# SUP_3_3_FMC.net
KiCad netlist of a schematic drawn in Altium Designer
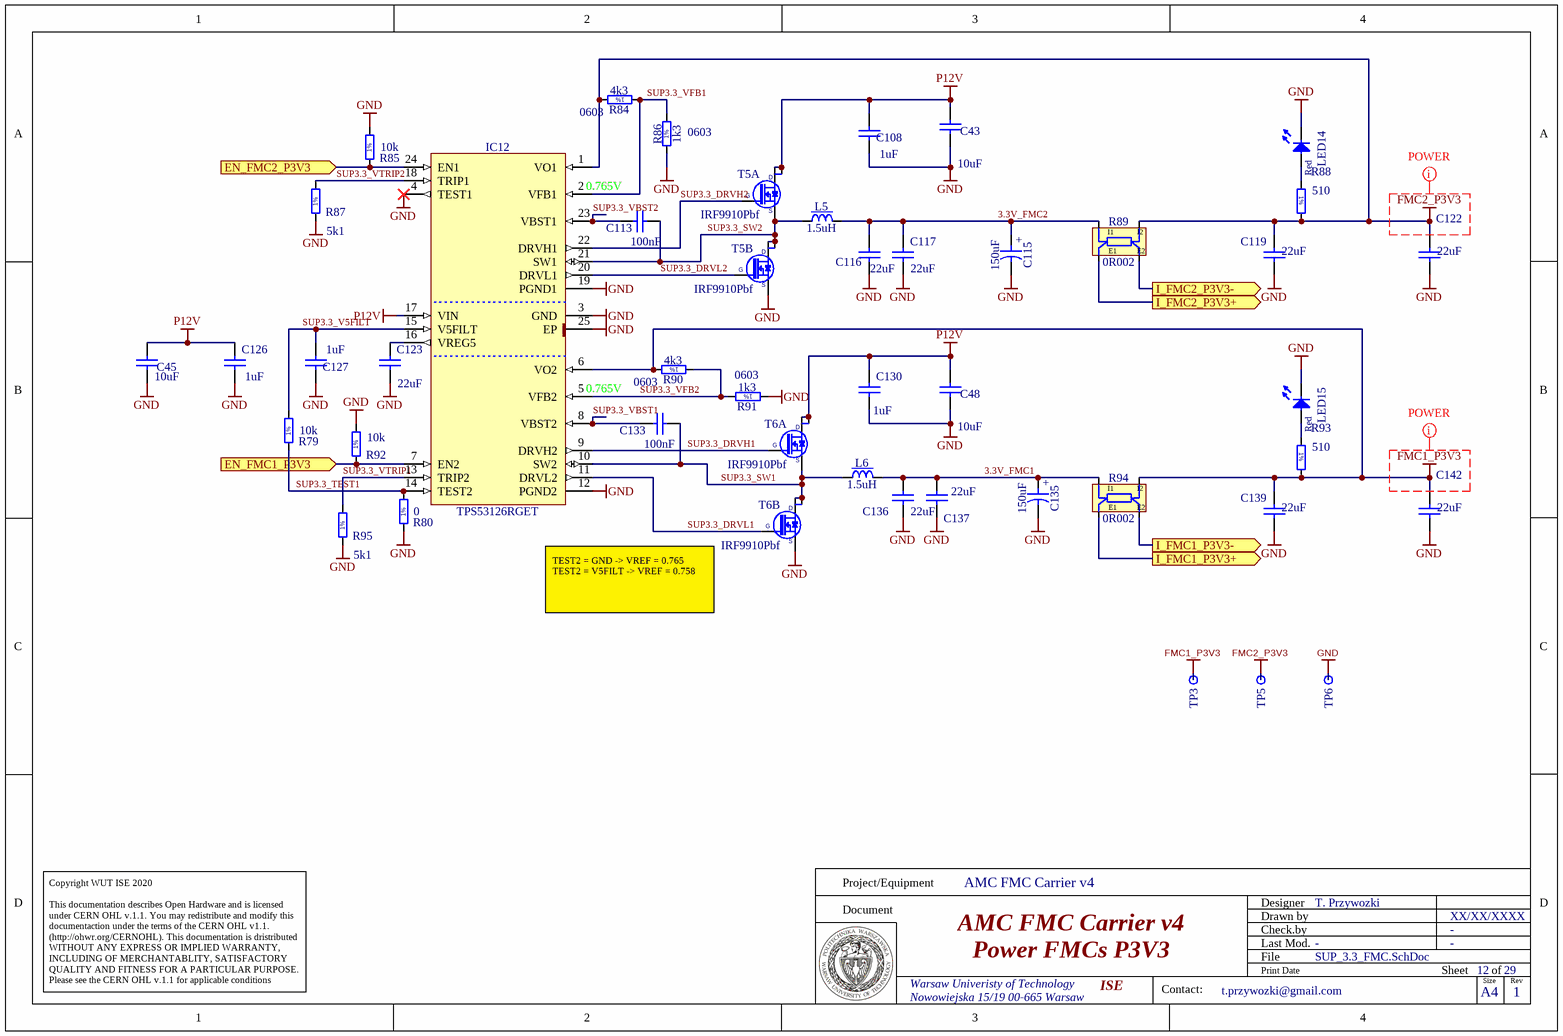
[diagram p0: SUP_3.3_FMC.SchDoc]

(export (version "E")
  (design (tool "Eeschema 10.0.6"))
  (components
    (comp (ref "C43")
      (value "10uF")
      (footprint "CAPC2012X135N")
      (description "Non-polarised capacitor")
      (fields
        (field (name "PART NUMBER") "CC0805_10UF_16V_10%_X5R")
        (field (name "VOLTAGE") "16V")
        (field (name "AUTHOR") "CERN DEM JLC")
      )
      (libsource (lib "Capacitors") (part "Capacitor - non polarized"))
    )
    (comp (ref "C45")
      (value "10uF")
      (footprint "CAPC2012X135N")
      (description "Non-polarised capacitor")
      (fields
        (field (name "PART NUMBER") "CC0805_10UF_16V_10%_X5R")
        (field (name "VOLTAGE") "16V")
        (field (name "AUTHOR") "CERN DEM JLC")
      )
      (libsource (lib "Capacitors") (part "Capacitor - non polarized"))
    )
    (comp (ref "C48")
      (value "10uF")
      (footprint "CAPC2012X135N")
      (description "Non-polarised capacitor")
      (fields
        (field (name "PART NUMBER") "CC0805_10UF_16V_10%_X5R")
        (field (name "VOLTAGE") "16V")
        (field (name "AUTHOR") "CERN DEM JLC")
      )
      (libsource (lib "Capacitors") (part "Capacitor - non polarized"))
    )
    (comp (ref "C108")
      (value "1uF")
      (footprint "CAPC1608X87N")
      (description "Non-polarised capacitor")
      (fields
        (field (name "PART NUMBER") "CC0603_1UF_16V_10%_X7R")
        (field (name "VOLTAGE") "16V")
        (field (name "AUTHOR") "CERN DEM JLC")
      )
      (libsource (lib "Capacitors") (part "Capacitor - non polarized"))
    )
    (comp (ref "C113")
      (value "100nF")
      (footprint "CAPC1005X55N")
      (description "Non-polarised capacitor")
      (fields
        (field (name "PART NUMBER") "CC0402_100NF_16V_10%_X7R")
        (field (name "VOLTAGE") "16V")
        (field (name "AUTHOR") "CERN DEM JLC")
      )
      (libsource (lib "Capacitors") (part "Capacitor - non polarized"))
    )
    (comp (ref "C115")
      (value "150uF")
      (footprint "CAPMP7343X200N")
      (description "Polarised capacitor")
      (fields
        (field (name "PART NUMBER") "CAEM7343-20_150UF_4V_20%_LESR0016")
        (field (name "VOLTAGE") "4V")
        (field (name "AUTHOR") "CERN DEM JLC")
      )
      (libsource (lib "Capacitors") (part "Capacitor - polarized"))
    )
    (comp (ref "C116")
      (value "22uF")
      (footprint "CAPC3216X180N")
      (description "Non-polarised capacitor")
      (fields
        (field (name "PART NUMBER") "CC1206_22UF_10V_10%_X7R")
        (field (name "VOLTAGE") "10V")
        (field (name "AUTHOR") "CERN DEM JLC")
      )
      (libsource (lib "Capacitors") (part "Capacitor - non polarized"))
    )
    (comp (ref "C117")
      (value "22uF")
      (footprint "CAPC3216X180N")
      (description "Non-polarised capacitor")
      (fields
        (field (name "PART NUMBER") "CC1206_22UF_10V_10%_X7R")
        (field (name "VOLTAGE") "10V")
        (field (name "AUTHOR") "CERN DEM JLC")
      )
      (libsource (lib "Capacitors") (part "Capacitor - non polarized"))
    )
    (comp (ref "C119")
      (value "22uF")
      (footprint "CAPC3216X180N")
      (description "Non-polarised capacitor")
      (fields
        (field (name "PART NUMBER") "CC1206_22UF_10V_10%_X7R")
        (field (name "VOLTAGE") "10V")
        (field (name "AUTHOR") "CERN DEM JLC")
      )
      (libsource (lib "Capacitors") (part "Capacitor - non polarized"))
    )
    (comp (ref "C122")
      (value "22uF")
      (footprint "CAPC3216X180N")
      (description "Non-polarised capacitor")
      (fields
        (field (name "PART NUMBER") "CC1206_22UF_10V_10%_X7R")
        (field (name "VOLTAGE") "10V")
        (field (name "AUTHOR") "CERN DEM JLC")
      )
      (libsource (lib "Capacitors") (part "Capacitor - non polarized"))
    )
    (comp (ref "C123")
      (value "22uF")
      (footprint "CAPC3216X180N")
      (description "Non-polarised capacitor")
      (fields
        (field (name "PART NUMBER") "CC1206_22UF_10V_10%_X7R")
        (field (name "VOLTAGE") "10V")
        (field (name "AUTHOR") "CERN DEM JLC")
      )
      (libsource (lib "Capacitors") (part "Capacitor - non polarized"))
    )
    (comp (ref "C126")
      (value "1uF")
      (footprint "CAPC1608X87N")
      (description "Non-polarised capacitor")
      (fields
        (field (name "PART NUMBER") "CC0603_1UF_16V_10%_X7R")
        (field (name "VOLTAGE") "16V")
        (field (name "AUTHOR") "CERN DEM JLC")
      )
      (libsource (lib "Capacitors") (part "Capacitor - non polarized"))
    )
    (comp (ref "C127")
      (value "1uF")
      (footprint "CAPC1608X87N")
      (description "Non-polarised capacitor")
      (fields
        (field (name "PART NUMBER") "CC0603_1UF_16V_10%_X7R")
        (field (name "VOLTAGE") "16V")
        (field (name "AUTHOR") "CERN DEM JLC")
      )
      (libsource (lib "Capacitors") (part "Capacitor - non polarized"))
    )
    (comp (ref "C130")
      (value "1uF")
      (footprint "CAPC1608X87N")
      (description "Non-polarised capacitor")
      (fields
        (field (name "PART NUMBER") "CC0603_1UF_16V_10%_X7R")
        (field (name "VOLTAGE") "16V")
        (field (name "AUTHOR") "CERN DEM JLC")
      )
      (libsource (lib "Capacitors") (part "Capacitor - non polarized"))
    )
    (comp (ref "C133")
      (value "100nF")
      (footprint "CAPC1005X55N")
      (description "Non-polarised capacitor")
      (fields
        (field (name "PART NUMBER") "CC0402_100NF_16V_10%_X7R")
        (field (name "VOLTAGE") "16V")
        (field (name "AUTHOR") "CERN DEM JLC")
      )
      (libsource (lib "Capacitors") (part "Capacitor - non polarized"))
    )
    (comp (ref "C135")
      (value "150uF")
      (footprint "CAPMP7343X200N")
      (description "Polarised capacitor")
      (fields
        (field (name "PART NUMBER") "CAEM7343-20_150UF_4V_20%_LESR0016")
        (field (name "VOLTAGE") "4V")
        (field (name "AUTHOR") "CERN DEM JLC")
      )
      (libsource (lib "Capacitors") (part "Capacitor - polarized"))
    )
    (comp (ref "C136")
      (value "22uF")
      (footprint "CAPC3216X180N")
      (description "Non-polarised capacitor")
      (fields
        (field (name "PART NUMBER") "CC1206_22UF_10V_10%_X7R")
        (field (name "VOLTAGE") "10V")
        (field (name "AUTHOR") "CERN DEM JLC")
      )
      (libsource (lib "Capacitors") (part "Capacitor - non polarized"))
    )
    (comp (ref "C137")
      (value "22uF")
      (footprint "CAPC3216X180N")
      (description "Non-polarised capacitor")
      (fields
        (field (name "PART NUMBER") "CC1206_22UF_10V_10%_X7R")
        (field (name "VOLTAGE") "10V")
        (field (name "AUTHOR") "CERN DEM JLC")
      )
      (libsource (lib "Capacitors") (part "Capacitor - non polarized"))
    )
    (comp (ref "C139")
      (value "22uF")
      (footprint "CAPC3216X180N")
      (description "Non-polarised capacitor")
      (fields
        (field (name "PART NUMBER") "CC1206_22UF_10V_10%_X7R")
        (field (name "VOLTAGE") "10V")
        (field (name "AUTHOR") "CERN DEM JLC")
      )
      (libsource (lib "Capacitors") (part "Capacitor - non polarized"))
    )
    (comp (ref "C142")
      (value "22uF")
      (footprint "CAPC3216X180N")
      (description "Non-polarised capacitor")
      (fields
        (field (name "PART NUMBER") "CC1206_22UF_10V_10%_X7R")
        (field (name "VOLTAGE") "10V")
        (field (name "AUTHOR") "CERN DEM JLC")
      )
      (libsource (lib "Capacitors") (part "Capacitor - non polarized"))
    )
    (comp (ref "IC12")
      (value "TPS53126RGET")
      (footprint "QFN50P400X400X100-25N-S255")
      (description "Dual Synchronous Step-Down Controller For Low Voltage Power Rails")
      (fields (field (name "MANUFACTURER") "TEXAS INSTRUMENTS") (field (name "AUTHOR") "CERN DEM JLC"))
      (libsource (lib "ICs And Semiconductors") (part "TPS53126RGET"))
    )
    (comp (ref "L5")
      (value "1.5uH")
      (footprint "IND_TDK_SPM6530")
      (description "Inductor With Core")
      (fields
        (field (name "PART NUMBER") "IND_1.5UH_20%_TDK_SPM6530")
        (field (name "POWER") "11A")
        (field (name "AUTHOR") "CERN DEM MR")
      )
      (libsource (lib "Inductors & Transformers") (part "Inductor With Magnetic core"))
    )
    (comp (ref "L6")
      (value "1.5uH")
      (footprint "IND_TDK_SPM6530")
      (description "Inductor With Core")
      (fields
        (field (name "PART NUMBER") "IND_1.5UH_20%_TDK_SPM6530")
        (field (name "POWER") "11A")
        (field (name "AUTHOR") "CERN DEM MR")
      )
      (libsource (lib "Inductors & Transformers") (part "Inductor With Magnetic core"))
    )
    (comp (ref "LED14")
      (value "Red")
      (footprint "LED_KINGBRIGHT_KPH-1608SURCK")
      (description "LED Red 1C 2A")
      (fields
        (field (name "PART NUMBER") "LED_KINGBRIGHT_KPH-1608SURCK")
        (field (name "MANUFACTURER") "KINGBRIGHT")
        (field (name "AUTHOR") "CERN DEM JLC")
      )
      (libsource (lib "ICs And Semiconductors") (part "LED Red 1C 2A"))
    )
    (comp (ref "LED15")
      (value "Red")
      (footprint "LED_KINGBRIGHT_KPH-1608SURCK")
      (description "LED Red 1C 2A")
      (fields
        (field (name "PART NUMBER") "LED_KINGBRIGHT_KPH-1608SURCK")
        (field (name "MANUFACTURER") "KINGBRIGHT")
        (field (name "AUTHOR") "CERN DEM JLC")
      )
      (libsource (lib "ICs And Semiconductors") (part "LED Red 1C 2A"))
    )
    (comp (ref "R79")
      (value "10k")
      (footprint "RESC1005X40N")
      (description "Resistor - 1%")
      (fields
        (field (name "PART NUMBER") "R0402_10K_1%_0.0625W_100PPM")
        (field (name "POWER") "0.0625W")
        (field (name "AUTHOR") "CERN DEM JLC")
      )
      (libsource (lib "Resistors") (part "Resistor - 1%"))
    )
    (comp (ref "R80")
      (value "0")
      (footprint "RESC1005X40N")
      (description "Resistor - 1%")
      (fields
        (field (name "PART NUMBER") "R0402_0R_JUMPER")
        (field (name "MANUFACTURER") "GENERIC")
        (field (name "AUTHOR") "CERN DEM JLC")
      )
      (libsource (lib "Resistors") (part "Resistor - 1%"))
    )
    (comp (ref "R84")
      (value "4k3")
      (footprint "RESC1608X55N")
      (description "Resistor - 1%")
      (fields
        (field (name "PART NUMBER") "R0603_4K3_1%_0.1W_100PPM")
        (field (name "POWER") "0.1W")
        (field (name "CASE") "0603")
        (field (name "AUTHOR") "CERN DEM JLC")
      )
      (libsource (lib "Resistors") (part "Resistor - 1%"))
    )
    (comp (ref "R85")
      (value "10k")
      (footprint "RESC1005X40N")
      (description "Resistor - 1%")
      (fields
        (field (name "PART NUMBER") "R0402_10K_1%_0.0625W_100PPM")
        (field (name "POWER") "0.0625W")
        (field (name "AUTHOR") "CERN DEM JLC")
      )
      (libsource (lib "Resistors") (part "Resistor - 1%"))
    )
    (comp (ref "R86")
      (value "1k3")
      (footprint "RESC1608X55N")
      (description "Resistor - 1%")
      (fields
        (field (name "PART NUMBER") "R0603_1K3_1%_0.1W_100PPM")
        (field (name "POWER") "0.1W")
        (field (name "CASE") "0603")
        (field (name "AUTHOR") "CERN DEM JLC")
      )
      (libsource (lib "Resistors") (part "Resistor - 1%"))
    )
    (comp (ref "R87")
      (value "5k1")
      (footprint "RESC1608X55N")
      (description "Resistor - 1%")
      (fields
        (field (name "PART NUMBER") "R0603_5K1_1%_0.1W_100PPM")
        (field (name "POWER") "0.1W")
        (field (name "AUTHOR") "CERN DEM JLC")
      )
      (libsource (lib "Resistors") (part "Resistor - 1%"))
    )
    (comp (ref "R88")
      (value "510")
      (footprint "RESC1005X40N")
      (description "Resistor - 1%")
      (fields
        (field (name "PART NUMBER") "R0402_510R_1%_0.0625W_100PPM")
        (field (name "POWER") "0.0625W")
        (field (name "AUTHOR") "CERN DEM JLC")
      )
      (libsource (lib "Resistors") (part "Resistor - 1%"))
    )
    (comp (ref "R89")
      (value "0R002")
      (footprint "RES_VISHAY_WSK2512_0R005-0R2")
      (description "Power and Current Sensing Resistor")
      (fields
        (field (name "PART NUMBER") "R2512_0R002_1%_1W_35PPM_VISHAY_WSK")
        (field (name "POWER") "1W")
        (field (name "AUTHOR") "CERN DEM MR")
      )
      (libsource (lib "Resistors") (part "Current Sense Resistor"))
    )
    (comp (ref "R90")
      (value "4k3")
      (footprint "RESC1608X55N")
      (description "Resistor - 1%")
      (fields
        (field (name "PART NUMBER") "R0603_4K3_1%_0.1W_100PPM")
        (field (name "POWER") "0.1W")
        (field (name "CASE") "0603")
        (field (name "AUTHOR") "CERN DEM JLC")
      )
      (libsource (lib "Resistors") (part "Resistor - 1%"))
    )
    (comp (ref "R91")
      (value "1k3")
      (footprint "RESC1608X55N")
      (description "Resistor - 1%")
      (fields
        (field (name "PART NUMBER") "R0603_1K3_1%_0.1W_100PPM")
        (field (name "POWER") "0.1W")
        (field (name "CASE") "0603")
        (field (name "AUTHOR") "CERN DEM JLC")
      )
      (libsource (lib "Resistors") (part "Resistor - 1%"))
    )
    (comp (ref "R92")
      (value "10k")
      (footprint "RESC1005X40N")
      (description "Resistor - 1%")
      (fields
        (field (name "PART NUMBER") "R0402_10K_1%_0.0625W_100PPM")
        (field (name "POWER") "0.0625W")
        (field (name "AUTHOR") "CERN DEM JLC")
      )
      (libsource (lib "Resistors") (part "Resistor - 1%"))
    )
    (comp (ref "R93")
      (value "510")
      (footprint "RESC1005X40N")
      (description "Resistor - 1%")
      (fields
        (field (name "PART NUMBER") "R0402_510R_1%_0.0625W_100PPM")
        (field (name "POWER") "0.0625W")
        (field (name "AUTHOR") "CERN DEM JLC")
      )
      (libsource (lib "Resistors") (part "Resistor - 1%"))
    )
    (comp (ref "R94")
      (value "0R002")
      (footprint "RES_VISHAY_WSK2512_0R005-0R2")
      (description "Power and Current Sensing Resistor")
      (fields
        (field (name "PART NUMBER") "R2512_0R002_1%_1W_35PPM_VISHAY_WSK")
        (field (name "POWER") "1W")
        (field (name "AUTHOR") "CERN DEM MR")
      )
      (libsource (lib "Resistors") (part "Current Sense Resistor"))
    )
    (comp (ref "R95")
      (value "5k1")
      (footprint "RESC1608X55N")
      (description "Resistor - 1%")
      (fields
        (field (name "PART NUMBER") "R0603_5K1_1%_0.1W_100PPM")
        (field (name "POWER") "0.1W")
        (field (name "AUTHOR") "CERN DEM JLC")
      )
      (libsource (lib "Resistors") (part "Resistor - 1%"))
    )
    (comp (ref "T5")
      (value "IRF9910Pbf")
      (footprint "SOIC127P600X175-8N")
      (description "Dual SO-8 MOSFET For POL Cconverter")
      (fields (field (name "MANUFACTURER") "INTERNATIONAL RECTIFIER") (field (name "AUTHOR") "CERN DEM JLC"))
      (libsource (lib "ICs And Semiconductors") (part "IRF9910"))
    )
    (comp (ref "T6")
      (value "IRF9910Pbf")
      (footprint "SOIC127P600X175-8N")
      (description "Dual SO-8 MOSFET For POL Cconverter")
      (fields (field (name "MANUFACTURER") "INTERNATIONAL RECTIFIER") (field (name "AUTHOR") "CERN DEM JLC"))
      (libsource (lib "ICs And Semiconductors") (part "IRF9910"))
    )
    (comp (ref "TP3")
      (value "Test Point")
      (footprint "TPS127")
      (fields (field (name "PART NUMBER") "SMD_PAD_1.27X1.27MM") (field (name "AUTHOR") "CERN DEM JLC"))
      (libsource (lib "Eletro-mechanical") (part "Test Point"))
    )
    (comp (ref "TP5")
      (value "Test Point")
      (footprint "TPS127")
      (fields (field (name "PART NUMBER") "SMD_PAD_1.27X1.27MM") (field (name "AUTHOR") "CERN DEM JLC"))
      (libsource (lib "Eletro-mechanical") (part "Test Point"))
    )
    (comp (ref "TP6")
      (value "Test Point")
      (footprint "TPS127")
      (fields (field (name "PART NUMBER") "SMD_PAD_1.27X1.27MM") (field (name "AUTHOR") "CERN DEM JLC"))
      (libsource (lib "Eletro-mechanical") (part "Test Point"))
    )
  )
  (nets
    (net (code "1") (name "/3.3V_FMC1") (class "Default")
      (node (ref "C135") (pin "1") (pinfunction "1_1") (pintype "passive"))
      (node (ref "C136") (pin "1") (pinfunction "1_1") (pintype "passive"))
      (node (ref "C137") (pin "1") (pinfunction "1_1") (pintype "passive"))
      (node (ref "L6") (pin "2") (pinfunction "2_2") (pintype "passive"))
      (node (ref "R94") (pin "I1") (pinfunction "I1_I1") (pintype "passive"))
    )
    (net (code "2") (name "/3.3V_FMC2") (class "Default")
      (node (ref "C115") (pin "1") (pinfunction "1_1") (pintype "passive"))
      (node (ref "C116") (pin "1") (pinfunction "1_1") (pintype "passive"))
      (node (ref "C117") (pin "1") (pinfunction "1_1") (pintype "passive"))
      (node (ref "L5") (pin "2") (pinfunction "2_2") (pintype "passive"))
      (node (ref "R89") (pin "I1") (pinfunction "I1_I1") (pintype "passive"))
    )
    (net (code "3") (name "/EN_FMC1_P3V3") (class "Default")
      (node (ref "IC12") (pin "7") (pinfunction "EN2_7") (pintype "input"))
      (node (ref "R92") (pin "1") (pinfunction "1_1") (pintype "passive"))
    )
    (net (code "4") (name "/EN_FMC2_P3V3") (class "Default")
      (node (ref "IC12") (pin "24") (pinfunction "EN1_24") (pintype "input"))
      (node (ref "R85") (pin "1") (pinfunction "1_1") (pintype "passive"))
    )
    (net (code "5") (name "/I_FMC1_P3V3+") (class "Default")
      (node (ref "R94") (pin "E1") (pinfunction "E1_E1") (pintype "passive"))
    )
    (net (code "6") (name "/I_FMC1_P3V3-") (class "Default")
      (node (ref "R94") (pin "E2") (pinfunction "E2_E2") (pintype "passive"))
    )
    (net (code "7") (name "/I_FMC2_P3V3+") (class "Default")
      (node (ref "R89") (pin "E1") (pinfunction "E1_E1") (pintype "passive"))
    )
    (net (code "8") (name "/I_FMC2_P3V3-") (class "Default")
      (node (ref "R89") (pin "E2") (pinfunction "E2_E2") (pintype "passive"))
    )
    (net (code "9") (name "/SUP3.3_DRVH1") (class "Default")
      (node (ref "IC12") (pin "9") (pinfunction "DRVH2_9") (pintype "output"))
      (node (ref "T6") (pin "4") (pinfunction "G_4") (pintype "passive"))
    )
    (net (code "10") (name "/SUP3.3_DRVH2") (class "Default")
      (node (ref "IC12") (pin "22") (pinfunction "DRVH1_22") (pintype "output"))
      (node (ref "T5") (pin "4") (pinfunction "G_4") (pintype "passive"))
    )
    (net (code "11") (name "/SUP3.3_DRVL1") (class "Default")
      (node (ref "IC12") (pin "11") (pinfunction "DRVL2_11") (pintype "output"))
      (node (ref "T6") (pin "2") (pinfunction "G_2") (pintype "passive"))
    )
    (net (code "12") (name "/SUP3.3_DRVL2") (class "Default")
      (node (ref "IC12") (pin "20") (pinfunction "DRVL1_20") (pintype "output"))
      (node (ref "T5") (pin "2") (pinfunction "G_2") (pintype "passive"))
    )
    (net (code "13") (name "/SUP3.3_SW1") (class "Default")
      (node (ref "C133") (pin "1") (pinfunction "1_1") (pintype "passive"))
      (node (ref "IC12") (pin "10") (pinfunction "SW2_10") (pintype "bidirectional"))
      (node (ref "L6") (pin "1") (pinfunction "1_1") (pintype "passive"))
      (node (ref "T6") (pin "3") (pinfunction "S_3") (pintype "passive"))
      (node (ref "T6") (pin "7") (pinfunction "D_7") (pintype "passive"))
      (node (ref "T6") (pin "8") (pinfunction "D_8") (pintype "passive"))
    )
    (net (code "14") (name "/SUP3.3_SW2") (class "Default")
      (node (ref "C113") (pin "1") (pinfunction "1_1") (pintype "passive"))
      (node (ref "IC12") (pin "21") (pinfunction "SW1_21") (pintype "bidirectional"))
      (node (ref "L5") (pin "1") (pinfunction "1_1") (pintype "passive"))
      (node (ref "T5") (pin "3") (pinfunction "S_3") (pintype "passive"))
      (node (ref "T5") (pin "7") (pinfunction "D_7") (pintype "passive"))
      (node (ref "T5") (pin "8") (pinfunction "D_8") (pintype "passive"))
    )
    (net (code "15") (name "/SUP3.3_TEST1") (class "Default")
      (node (ref "IC12") (pin "14") (pinfunction "TEST2_14") (pintype "input"))
      (node (ref "R79") (pin "1") (pinfunction "1_1") (pintype "passive"))
      (node (ref "R80") (pin "2") (pinfunction "2_2") (pintype "passive"))
    )
    (net (code "16") (name "/SUP3.3_V5FILT") (class "Default")
      (node (ref "C127") (pin "2") (pinfunction "2_2") (pintype "passive"))
      (node (ref "IC12") (pin "15") (pinfunction "V5FILT_15") (pintype "input"))
      (node (ref "R79") (pin "2") (pinfunction "2_2") (pintype "passive"))
    )
    (net (code "17") (name "/SUP3.3_VBST1") (class "Default")
      (node (ref "C133") (pin "2") (pinfunction "2_2") (pintype "passive"))
      (node (ref "IC12") (pin "8") (pinfunction "VBST2_8") (pintype "input"))
    )
    (net (code "18") (name "/SUP3.3_VBST2") (class "Default")
      (node (ref "C113") (pin "2") (pinfunction "2_2") (pintype "passive"))
      (node (ref "IC12") (pin "23") (pinfunction "VBST1_23") (pintype "input"))
    )
    (net (code "19") (name "/SUP3.3_VFB1") (class "Default")
      (node (ref "IC12") (pin "2") (pinfunction "VFB1_2") (pintype "input"))
      (node (ref "R84") (pin "1") (pinfunction "1_1") (pintype "passive"))
      (node (ref "R86") (pin "2") (pinfunction "2_2") (pintype "passive"))
    )
    (net (code "20") (name "/SUP3.3_VFB2") (class "Default")
      (node (ref "IC12") (pin "5") (pinfunction "VFB2_5") (pintype "input"))
      (node (ref "R90") (pin "1") (pinfunction "1_1") (pintype "passive"))
      (node (ref "R91") (pin "2") (pinfunction "2_2") (pintype "passive"))
    )
    (net (code "21") (name "/SUP3.3_VTRIP1") (class "Default")
      (node (ref "IC12") (pin "13") (pinfunction "TRIP2_13") (pintype "input"))
      (node (ref "R95") (pin "2") (pinfunction "2_2") (pintype "passive"))
    )
    (net (code "22") (name "/SUP3.3_VTRIP2") (class "Default")
      (node (ref "IC12") (pin "18") (pinfunction "TRIP1_18") (pintype "input"))
      (node (ref "R87") (pin "2") (pinfunction "2_2") (pintype "passive"))
    )
    (net (code "23") (name "FMC1_P3V3") (class "Default")
      (node (ref "C139") (pin "1") (pinfunction "1_1") (pintype "passive"))
      (node (ref "C142") (pin "1") (pinfunction "1_1") (pintype "passive"))
      (node (ref "IC12") (pin "6") (pinfunction "VO2_6") (pintype "input"))
      (node (ref "R90") (pin "2") (pinfunction "2_2") (pintype "passive"))
      (node (ref "R93") (pin "2") (pinfunction "2_2") (pintype "passive"))
      (node (ref "R94") (pin "I2") (pinfunction "I2_I2") (pintype "passive"))
      (node (ref "TP3") (pin "1") (pinfunction "1_1") (pintype "bidirectional"))
    )
    (net (code "24") (name "FMC2_P3V3") (class "Default")
      (node (ref "C119") (pin "1") (pinfunction "1_1") (pintype "passive"))
      (node (ref "C122") (pin "1") (pinfunction "1_1") (pintype "passive"))
      (node (ref "IC12") (pin "1") (pinfunction "VO1_1") (pintype "input"))
      (node (ref "R84") (pin "2") (pinfunction "2_2") (pintype "passive"))
      (node (ref "R88") (pin "2") (pinfunction "2_2") (pintype "passive"))
      (node (ref "R89") (pin "I2") (pinfunction "I2_I2") (pintype "passive"))
      (node (ref "TP5") (pin "1") (pinfunction "1_1") (pintype "bidirectional"))
    )
    (net (code "25") (name "GND") (class "Default")
      (node (ref "C108") (pin "1") (pinfunction "1_1") (pintype "passive"))
      (node (ref "C115") (pin "2") (pinfunction "2_2") (pintype "passive"))
      (node (ref "C116") (pin "2") (pinfunction "2_2") (pintype "passive"))
      (node (ref "C117") (pin "2") (pinfunction "2_2") (pintype "passive"))
      (node (ref "C119") (pin "2") (pinfunction "2_2") (pintype "passive"))
      (node (ref "C122") (pin "2") (pinfunction "2_2") (pintype "passive"))
      (node (ref "C123") (pin "1") (pinfunction "1_1") (pintype "passive"))
      (node (ref "C126") (pin "1") (pinfunction "1_1") (pintype "passive"))
      (node (ref "C127") (pin "1") (pinfunction "1_1") (pintype "passive"))
      (node (ref "C130") (pin "1") (pinfunction "1_1") (pintype "passive"))
      (node (ref "C135") (pin "2") (pinfunction "2_2") (pintype "passive"))
      (node (ref "C136") (pin "2") (pinfunction "2_2") (pintype "passive"))
      (node (ref "C137") (pin "2") (pinfunction "2_2") (pintype "passive"))
      (node (ref "C139") (pin "2") (pinfunction "2_2") (pintype "passive"))
      (node (ref "C142") (pin "2") (pinfunction "2_2") (pintype "passive"))
      (node (ref "C43") (pin "1") (pinfunction "1_1") (pintype "passive"))
      (node (ref "C45") (pin "1") (pinfunction "1_1") (pintype "passive"))
      (node (ref "C48") (pin "1") (pinfunction "1_1") (pintype "passive"))
      (node (ref "IC12") (pin "12") (pinfunction "PGND2_12") (pintype "power_in"))
      (node (ref "IC12") (pin "19") (pinfunction "PGND1_19") (pintype "power_in"))
      (node (ref "IC12") (pin "25") (pinfunction "EP_25") (pintype "power_in"))
      (node (ref "IC12") (pin "3") (pinfunction "GND_3") (pintype "power_in"))
      (node (ref "IC12") (pin "4") (pinfunction "TEST1_4") (pintype "output"))
      (node (ref "LED14") (pin "1") (pinfunction "C_1") (pintype "passive"))
      (node (ref "LED15") (pin "1") (pinfunction "C_1") (pintype "passive"))
      (node (ref "R80") (pin "1") (pinfunction "1_1") (pintype "passive"))
      (node (ref "R85") (pin "2") (pinfunction "2_2") (pintype "passive"))
      (node (ref "R86") (pin "1") (pinfunction "1_1") (pintype "passive"))
      (node (ref "R87") (pin "1") (pinfunction "1_1") (pintype "passive"))
      (node (ref "R91") (pin "1") (pinfunction "1_1") (pintype "passive"))
      (node (ref "R92") (pin "2") (pinfunction "2_2") (pintype "passive"))
      (node (ref "R95") (pin "1") (pinfunction "1_1") (pintype "passive"))
      (node (ref "T5") (pin "1") (pinfunction "S_1") (pintype "passive"))
      (node (ref "T6") (pin "1") (pinfunction "S_1") (pintype "passive"))
      (node (ref "TP6") (pin "1") (pinfunction "1_1") (pintype "bidirectional"))
    )
    (net (code "26") (name "Net-(IC12-VREG5)") (class "Default")
      (node (ref "C123") (pin "2") (pinfunction "2_2") (pintype "passive"))
      (node (ref "IC12") (pin "16") (pinfunction "VREG5_16") (pintype "output"))
    )
    (net (code "27") (name "Net-(LED14-A)") (class "Default")
      (node (ref "LED14") (pin "2") (pinfunction "A_2") (pintype "passive"))
      (node (ref "R88") (pin "1") (pinfunction "1_1") (pintype "passive"))
    )
    (net (code "28") (name "Net-(LED15-A)") (class "Default")
      (node (ref "LED15") (pin "2") (pinfunction "A_2") (pintype "passive"))
      (node (ref "R93") (pin "1") (pinfunction "1_1") (pintype "passive"))
    )
    (net (code "29") (name "P12V") (class "Default")
      (node (ref "C108") (pin "2") (pinfunction "2_2") (pintype "passive"))
      (node (ref "C126") (pin "2") (pinfunction "2_2") (pintype "passive"))
      (node (ref "C130") (pin "2") (pinfunction "2_2") (pintype "passive"))
      (node (ref "C43") (pin "2") (pinfunction "2_2") (pintype "passive"))
      (node (ref "C45") (pin "2") (pinfunction "2_2") (pintype "passive"))
      (node (ref "C48") (pin "2") (pinfunction "2_2") (pintype "passive"))
      (node (ref "IC12") (pin "17") (pinfunction "VIN_17") (pintype "input"))
      (node (ref "T5") (pin "5") (pinfunction "D_5") (pintype "passive"))
      (node (ref "T5") (pin "6") (pinfunction "D_6") (pintype "passive"))
      (node (ref "T6") (pin "5") (pinfunction "D_5") (pintype "passive"))
      (node (ref "T6") (pin "6") (pinfunction "D_6") (pintype "passive"))
    )
  )
)
